# eBox_3G.net
KiCad netlist of a schematic drawn in Altium Designer
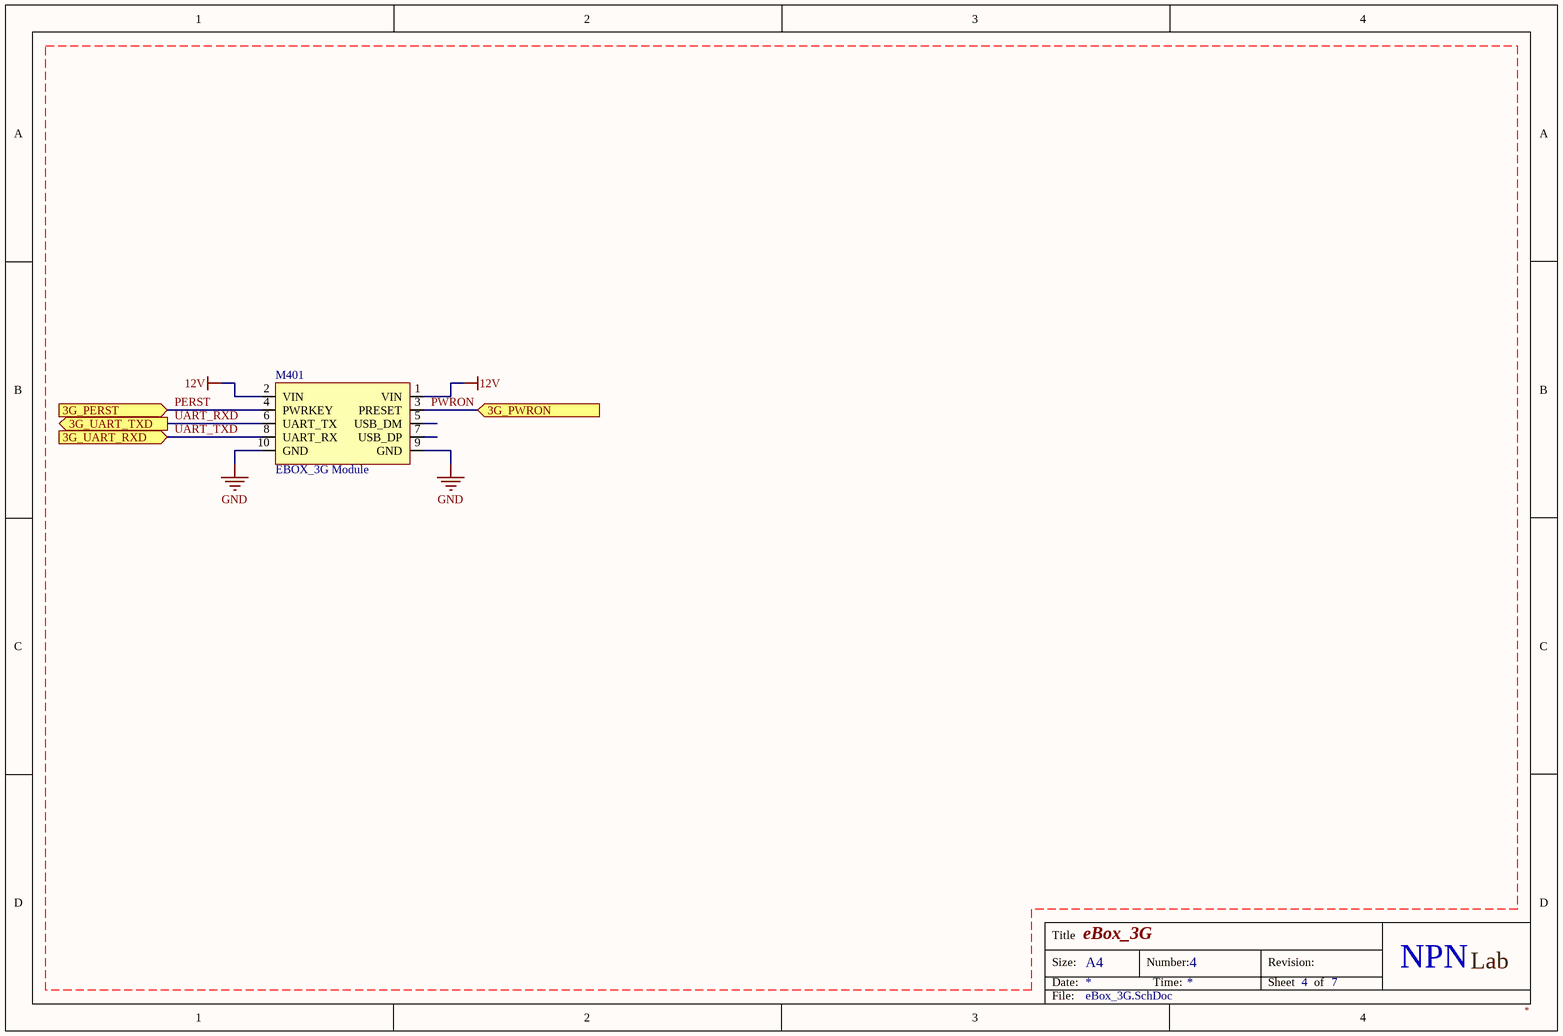
[diagram p0: eBox_3G.SchDoc]

(export (version "E")
  (design (tool "Eeschema 10.0.6"))
  (components
    (comp (ref "M401")
      (value "EBOX_3G Module")
      (footprint "EBOX_3G")
      (libsource (lib "Utilities") (part "EBOX_3G Module"))
    )
  )
  (nets
    (net (code "1") (name "/PERST") (class "Default")
      (node (ref "M401") (pin "4") (pinfunction "PWRKEY_4") (pintype "passive"))
    )
    (net (code "2") (name "/PWRON") (class "Default")
      (node (ref "M401") (pin "3") (pinfunction "PRESET_3") (pintype "passive"))
    )
    (net (code "3") (name "/UART_RXD") (class "Default")
      (node (ref "M401") (pin "6") (pinfunction "UART_TX_6") (pintype "passive"))
    )
    (net (code "4") (name "/UART_TXD") (class "Default")
      (node (ref "M401") (pin "8") (pinfunction "UART_RX_8") (pintype "passive"))
    )
    (net (code "5") (name "12V") (class "Default")
      (node (ref "M401") (pin "1") (pinfunction "VIN_1") (pintype "passive"))
      (node (ref "M401") (pin "2") (pinfunction "VIN_2") (pintype "passive"))
    )
    (net (code "6") (name "GND") (class "Default")
      (node (ref "M401") (pin "10") (pinfunction "GND_10") (pintype "passive"))
      (node (ref "M401") (pin "9") (pinfunction "GND_9") (pintype "passive"))
    )
    (net (code "7") (name "unconnected-(M401-USB_DM-Pad5)") (class "Default")
      (node (ref "M401") (pin "5") (pinfunction "USB_DM_5") (pintype "passive"))
    )
    (net (code "8") (name "unconnected-(M401-USB_DP-Pad7)") (class "Default")
      (node (ref "M401") (pin "7") (pinfunction "USB_DP_7") (pintype "passive"))
    )
  )
)
